# blumenland.net
KiCad netlist of a schematic drawn in EAGLE
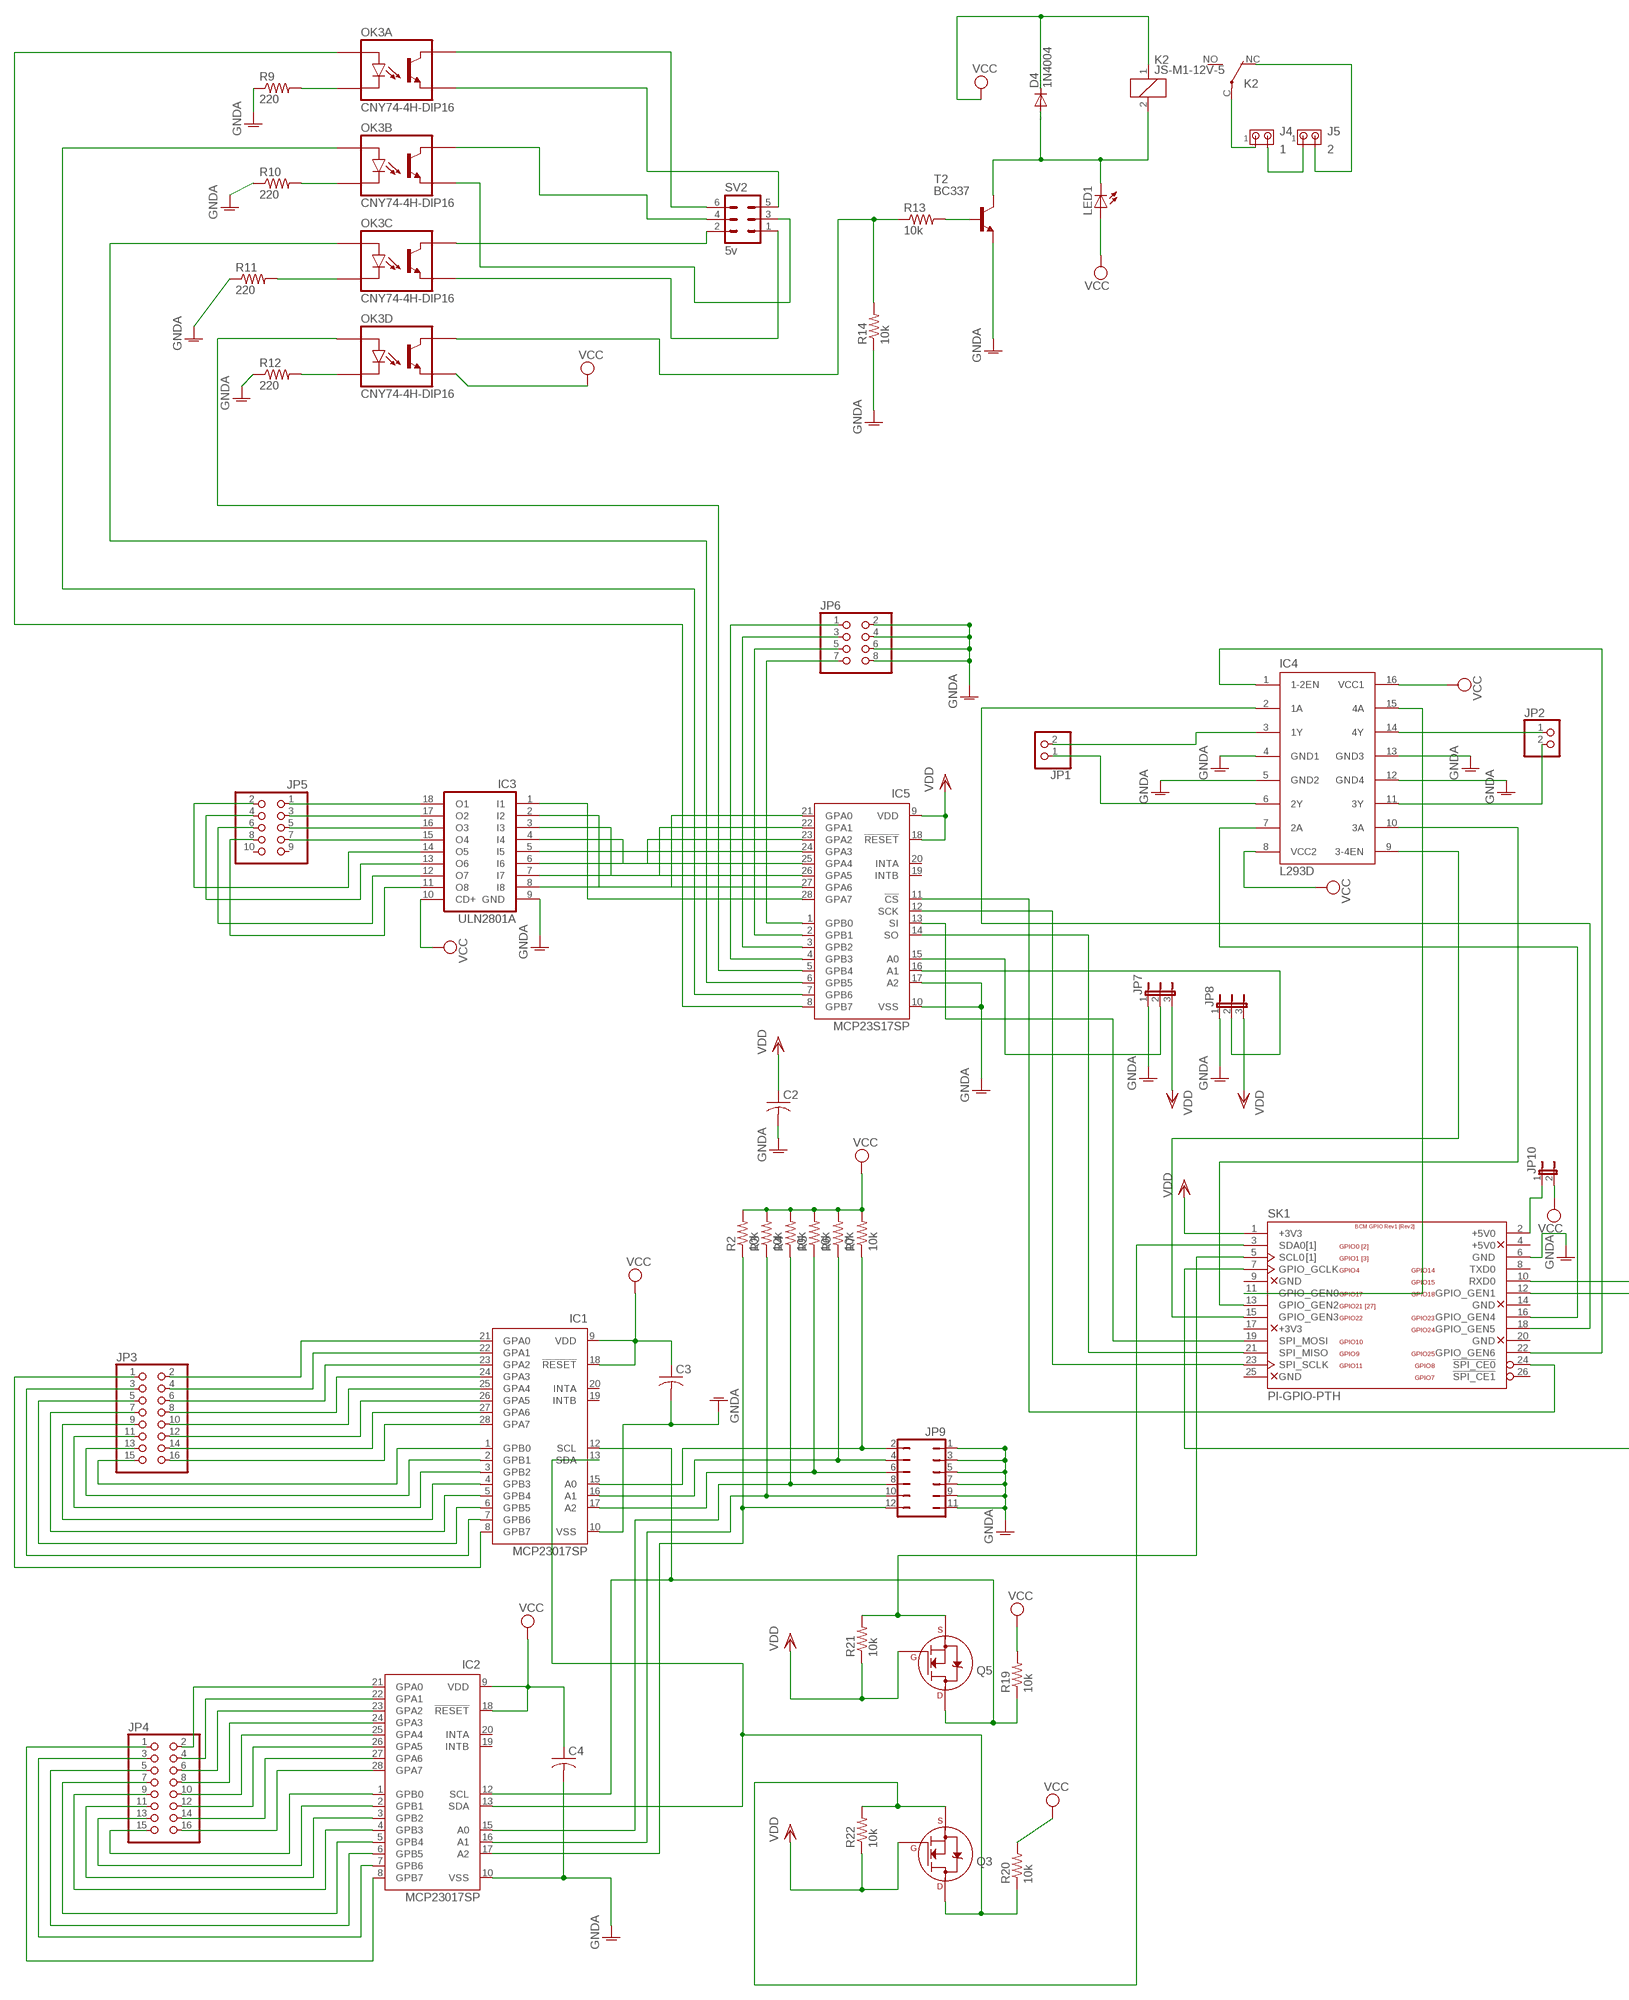
[diagram p0: schematic, sheet 1, part 1 of 2]
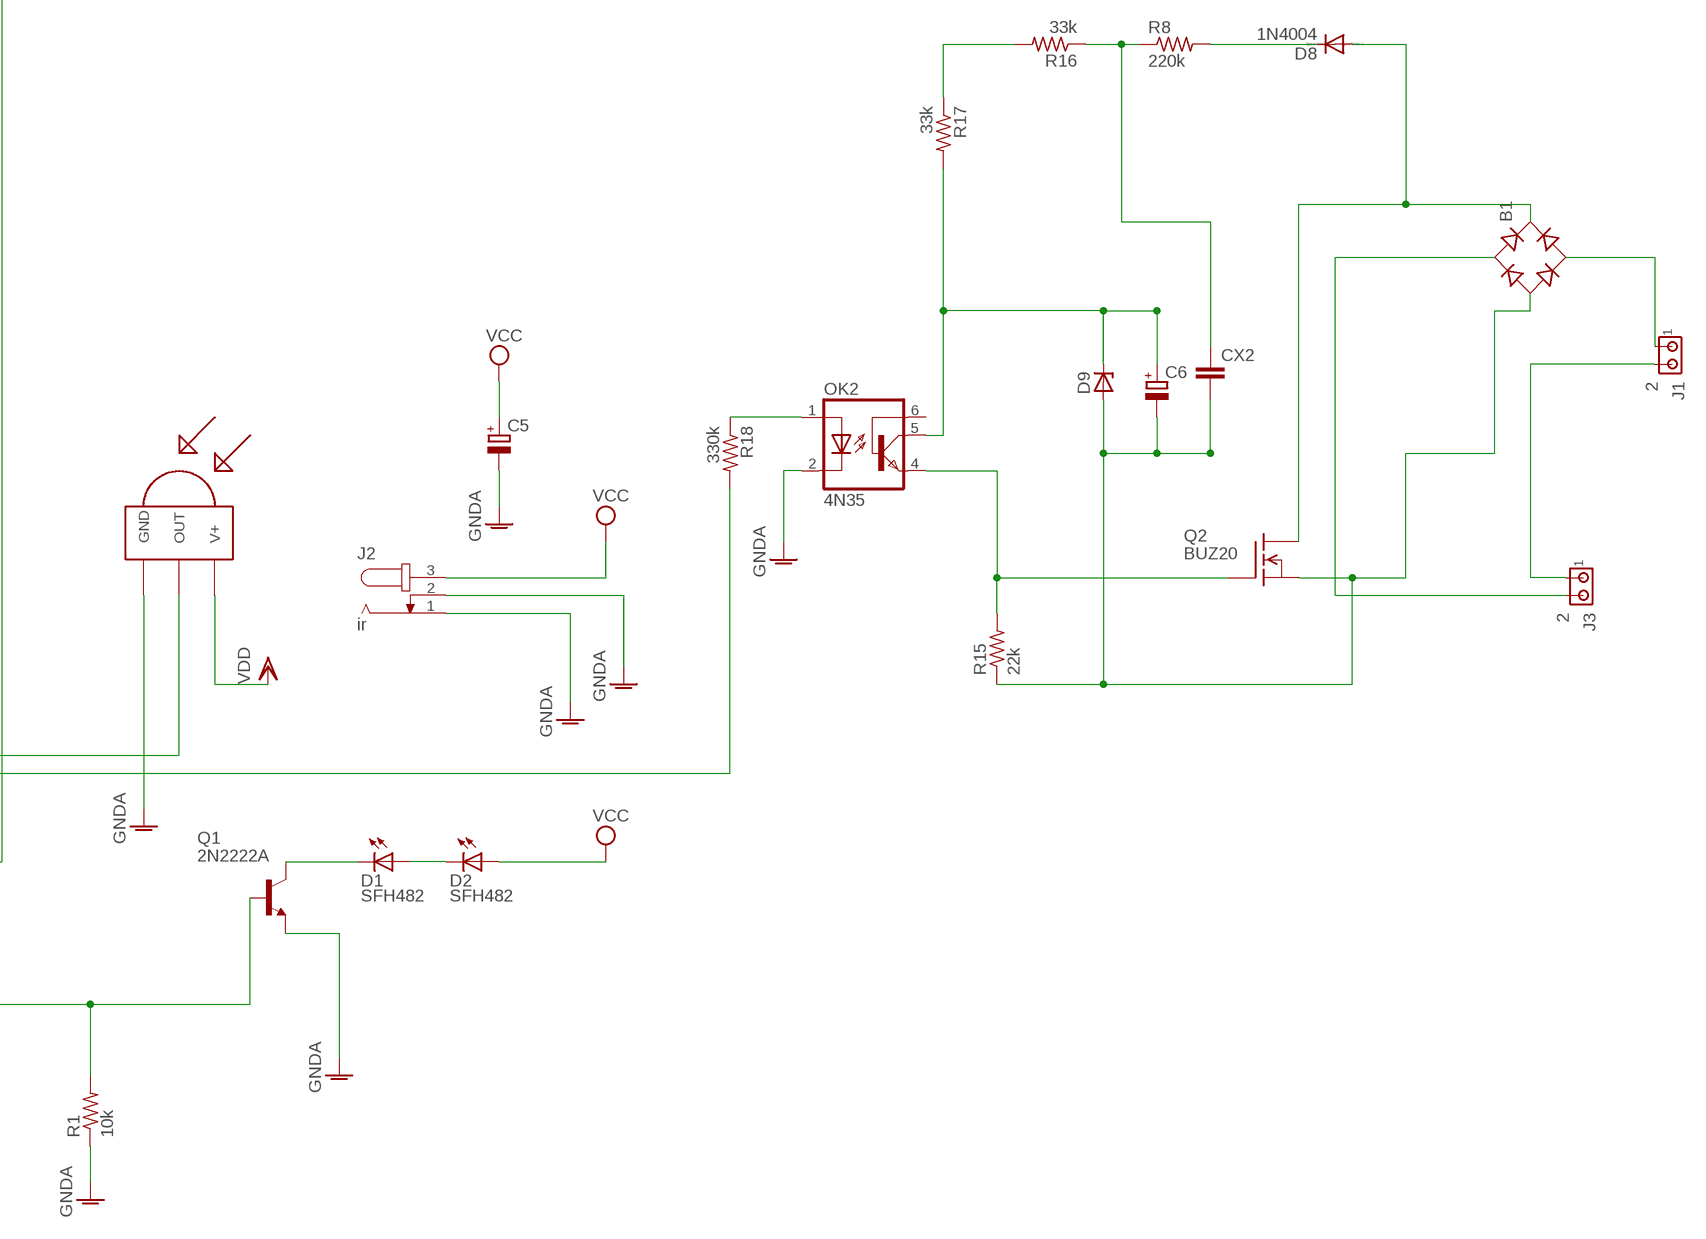
[diagram p1: schematic, sheet 1, part 2 of 2]

(export (version "E")
  (design (tool "Eeschema 10.0.6"))
  (components
    (comp (ref "B1")
      (value "RB1A")
      (footprint "eagle-import:RB1A")
      (libsource (lib "eagle-import") (part "RB1A"))
    )
    (comp (ref "C2")
      (value "C-US025-025X050")
      (footprint "eagle-import:C025-025X050")
      (libsource (lib "eagle-import") (part "C-US025-025X050"))
    )
    (comp (ref "C3")
      (value "C-US025-025X050")
      (footprint "eagle-import:C025-025X050")
      (libsource (lib "eagle-import") (part "C-US025-025X050"))
    )
    (comp (ref "C4")
      (value "C-US025-025X050")
      (footprint "eagle-import:C025-025X050")
      (libsource (lib "eagle-import") (part "C-US025-025X050"))
    )
    (comp (ref "C5")
      (value "CPOL-EUE2-5")
      (footprint "eagle-import:E2-5")
      (libsource (lib "eagle-import") (part "CPOL-EUE2-5"))
    )
    (comp (ref "C6")
      (value "CPOL-EUE2.5-5")
      (footprint "eagle-import:E2,5-5")
      (libsource (lib "eagle-import") (part "CPOL-EUE2.5-5"))
    )
    (comp (ref "CX2")
      (value "CXXC10B6")
      (footprint "eagle-import:XC10B6")
      (libsource (lib "eagle-import") (part "CXXC10B6"))
    )
    (comp (ref "D1")
      (value "SFH482")
      (footprint "eagle-import:SFH482")
      (libsource (lib "eagle-import") (part "SFH482"))
    )
    (comp (ref "D2")
      (value "SFH482")
      (footprint "eagle-import:SFH482")
      (libsource (lib "eagle-import") (part "SFH482"))
    )
    (comp (ref "D4")
      (value "1N4004")
      (footprint "eagle-import:DO41-10")
      (libsource (lib "eagle-import") (part "1N4004"))
    )
    (comp (ref "D8")
      (value "1N4004")
      (footprint "eagle-import:DO41-10")
      (libsource (lib "eagle-import") (part "1N4004"))
    )
    (comp (ref "D9")
      (value "ZENER-DIODEDO41Z10")
      (footprint "eagle-import:DO41Z10")
      (libsource (lib "eagle-import") (part "ZENER-DIODEDO41Z10"))
    )
    (comp (ref "IC1")
      (value "MCP23017SP")
      (footprint "eagle-import:DIL28-3")
      (fields (field (name "MF") "MICROCHIP") (field (name "MPN") "MCP23017-E/SP"))
      (libsource (lib "eagle-import") (part "MCP23017SP"))
    )
    (comp (ref "IC2")
      (value "MCP23017SP")
      (footprint "eagle-import:DIL28-3")
      (fields (field (name "MF") "MICROCHIP") (field (name "MPN") "MCP23017-E/SP"))
      (libsource (lib "eagle-import") (part "MCP23017SP"))
    )
    (comp (ref "IC3")
      (value "ULN2801A")
      (footprint "eagle-import:DIL18")
      (libsource (lib "eagle-import") (part "ULN2801A"))
    )
    (comp (ref "IC4")
      (value "L293D")
      (footprint "eagle-import:DIL16")
      (libsource (lib "eagle-import") (part "L293D"))
    )
    (comp (ref "IC5")
      (value "MCP23S17SP")
      (footprint "eagle-import:DIL28-3")
      (fields (field (name "MF") "MICROCHIP") (field (name "MPN") "MCP23S17-E/SP"))
      (libsource (lib "eagle-import") (part "MCP23S17SP"))
    )
    (comp (ref "J1")
      (value "2")
      (footprint "eagle-import:1X2MTA")
      (libsource (lib "eagle-import") (part "MTA02-156"))
    )
    (comp (ref "J2")
      (value "ir")
      (footprint "eagle-import:SPC4077")
      (libsource (lib "eagle-import") (part "JACK-PLUG0"))
    )
    (comp (ref "J3")
      (value "2")
      (footprint "eagle-import:1X2MTA")
      (libsource (lib "eagle-import") (part "MTA02-156"))
    )
    (comp (ref "J4")
      (value "1")
      (footprint "eagle-import:1X2MTA")
      (libsource (lib "eagle-import") (part "MTA02-156"))
    )
    (comp (ref "J5")
      (value "2")
      (footprint "eagle-import:1X2MTA")
      (libsource (lib "eagle-import") (part "MTA02-156"))
    )
    (comp (ref "JP1")
      (value "PINHD-1X2")
      (footprint "eagle-import:1X02")
      (libsource (lib "eagle-import") (part "PINHD-1X2"))
    )
    (comp (ref "JP2")
      (value "PINHD-1X2")
      (footprint "eagle-import:1X02")
      (libsource (lib "eagle-import") (part "PINHD-1X2"))
    )
    (comp (ref "JP3")
      (value "PINHD-2X8")
      (footprint "eagle-import:2X08")
      (libsource (lib "eagle-import") (part "PINHD-2X8"))
    )
    (comp (ref "JP4")
      (value "PINHD-2X8")
      (footprint "eagle-import:2X08")
      (libsource (lib "eagle-import") (part "PINHD-2X8"))
    )
    (comp (ref "JP5")
      (value "PINHD-2X5")
      (footprint "eagle-import:2X05")
      (libsource (lib "eagle-import") (part "PINHD-2X5"))
    )
    (comp (ref "JP6")
      (value "PINHD-2X4")
      (footprint "eagle-import:2X04")
      (libsource (lib "eagle-import") (part "PINHD-2X4"))
    )
    (comp (ref "JP7")
      (value "JP2E")
      (footprint "eagle-import:JP2")
      (libsource (lib "eagle-import") (part "JP2E"))
    )
    (comp (ref "JP8")
      (value "JP2E")
      (footprint "eagle-import:JP2")
      (libsource (lib "eagle-import") (part "JP2E"))
    )
    (comp (ref "JP9")
      (value "JP6Q")
      (footprint "eagle-import:JP6Q")
      (libsource (lib "eagle-import") (part "JP6Q"))
    )
    (comp (ref "JP10")
      (value "JP1E")
      (footprint "eagle-import:JP1")
      (libsource (lib "eagle-import") (part "JP1E"))
    )
    (comp (ref "K2")
      (value "JS-M1-12V-5")
      (footprint "eagle-import:JS-M")
      (fields (field (name "MF") "FARNELL") (field (name "MPN") "JSM1-12V-5"))
      (libsource (lib "eagle-import") (part "JS-M1-12V-5"))
    )
    (comp (ref "LED1")
      (value "LED5MM")
      (footprint "eagle-import:LED5MM")
      (libsource (lib "eagle-import") (part "LED5MM"))
    )
    (comp (ref "OK2")
      (value "4N35")
      (footprint "eagle-import:DIL06")
      (fields (field (name "MF") "FAIRCHILD SEMICONDUCTOR"))
      (libsource (lib "eagle-import") (part "4N35"))
    )
    (comp (ref "OK3")
      (value "CNY74-4H-DIP16")
      (footprint "eagle-import:DIL16-3")
      (libsource (lib "eagle-import") (part "CNY74-4H-DIP16"))
    )
    (comp (ref "Q1")
      (value "2N2222A")
      (footprint "eagle-import:TO18")
      (libsource (lib "eagle-import") (part "2N2222A"))
    )
    (comp (ref "Q2")
      (value "BUZ20")
      (footprint "eagle-import:TO220")
      (libsource (lib "eagle-import") (part "BUZ20"))
    )
    (comp (ref "Q3")
      (value "2N7000_TO92")
      (footprint "eagle-import:TO-92")
      (libsource (lib "eagle-import") (part "2N700_TO920"))
    )
    (comp (ref "Q5")
      (value "2N7000_TO92")
      (footprint "eagle-import:TO-92")
      (libsource (lib "eagle-import") (part "2N700_TO920"))
    )
    (comp (ref "R1")
      (value "10k")
      (footprint "eagle-import:0207_10")
      (libsource (lib "eagle-import") (part "R-US_0207/10"))
    )
    (comp (ref "R2")
      (value "10k")
      (footprint "eagle-import:0207_10")
      (libsource (lib "eagle-import") (part "R-US_0207/10"))
    )
    (comp (ref "R3")
      (value "10k")
      (footprint "eagle-import:0207_10")
      (libsource (lib "eagle-import") (part "R-US_0207/10"))
    )
    (comp (ref "R4")
      (value "10k")
      (footprint "eagle-import:0207_10")
      (libsource (lib "eagle-import") (part "R-US_0207/10"))
    )
    (comp (ref "R5")
      (value "10k")
      (footprint "eagle-import:0207_10")
      (libsource (lib "eagle-import") (part "R-US_0207/10"))
    )
    (comp (ref "R6")
      (value "10k")
      (footprint "eagle-import:0207_10")
      (libsource (lib "eagle-import") (part "R-US_0207/10"))
    )
    (comp (ref "R7")
      (value "10k")
      (footprint "eagle-import:0207_10")
      (libsource (lib "eagle-import") (part "R-US_0207/10"))
    )
    (comp (ref "R8")
      (value "220k")
      (footprint "eagle-import:0207_10")
      (libsource (lib "eagle-import") (part "R-US_0207/10"))
    )
    (comp (ref "R9")
      (value "220")
      (footprint "eagle-import:0204_7")
      (libsource (lib "eagle-import") (part "R-US_0204/7"))
    )
    (comp (ref "R10")
      (value "220")
      (footprint "eagle-import:0204_7")
      (libsource (lib "eagle-import") (part "R-US_0204/7"))
    )
    (comp (ref "R11")
      (value "220")
      (footprint "eagle-import:0204_7")
      (libsource (lib "eagle-import") (part "R-US_0204/7"))
    )
    (comp (ref "R12")
      (value "220")
      (footprint "eagle-import:0204_7")
      (libsource (lib "eagle-import") (part "R-US_0204/7"))
    )
    (comp (ref "R13")
      (value "10k")
      (footprint "eagle-import:0204_7")
      (libsource (lib "eagle-import") (part "R-US_0204/7"))
    )
    (comp (ref "R14")
      (value "10k")
      (footprint "eagle-import:0204_7")
      (libsource (lib "eagle-import") (part "R-US_0204/7"))
    )
    (comp (ref "R15")
      (value "22k")
      (footprint "eagle-import:0207_10")
      (libsource (lib "eagle-import") (part "R-US_0207/10"))
    )
    (comp (ref "R16")
      (value "33k")
      (footprint "eagle-import:0207_10")
      (libsource (lib "eagle-import") (part "R-US_0207/10"))
    )
    (comp (ref "R17")
      (value "33k")
      (footprint "eagle-import:0207_10")
      (libsource (lib "eagle-import") (part "R-US_0207/10"))
    )
    (comp (ref "R18")
      (value "330k")
      (footprint "eagle-import:0207_10")
      (libsource (lib "eagle-import") (part "R-US_0207/10"))
    )
    (comp (ref "R19")
      (value "10k")
      (footprint "eagle-import:0207_10")
      (libsource (lib "eagle-import") (part "R-US_0207/10"))
    )
    (comp (ref "R20")
      (value "10k")
      (footprint "eagle-import:0207_10")
      (libsource (lib "eagle-import") (part "R-US_0207/10"))
    )
    (comp (ref "R21")
      (value "10k")
      (footprint "eagle-import:0207_10")
      (libsource (lib "eagle-import") (part "R-US_0207/10"))
    )
    (comp (ref "R22")
      (value "10k")
      (footprint "eagle-import:0207_10")
      (libsource (lib "eagle-import") (part "R-US_0207/10"))
    )
    (comp (ref "SK1")
      (value "PI-GPIO-PTH")
      (footprint "eagle-import:GPIO-CONNECTOR")
      (libsource (lib "eagle-import") (part "PI-GPIO-PTH"))
    )
    (comp (ref "SV2")
      (value "5v")
      (footprint "eagle-import:MA03-2")
      (libsource (lib "eagle-import") (part "MA03-2"))
    )
    (comp (ref "T2")
      (value "BC337")
      (footprint "eagle-import:TO92")
      (libsource (lib "eagle-import") (part "BC337"))
    )
    (comp (ref "U$1")
      (value "TSOP4838")
      (footprint "eagle-import:TSOP18XX")
      (libsource (lib "eagle-import") (part "TSOP4838"))
    )
  )
  (nets
    (net (code "1") (name "GNDA") (class "Default")
      (node (ref "C2") (pin "2") (pinfunction "2_2") (pintype "passive"))
      (node (ref "C3") (pin "2") (pinfunction "2_2") (pintype "passive"))
      (node (ref "C4") (pin "2") (pinfunction "2_2") (pintype "passive"))
      (node (ref "C5") (pin "-") (pinfunction "-_-") (pintype "passive"))
      (node (ref "IC1") (pin "10") (pinfunction "VSS_10") (pintype "power_in"))
      (node (ref "IC2") (pin "10") (pinfunction "VSS_10") (pintype "power_in"))
      (node (ref "IC3") (pin "9") (pinfunction "GND_9") (pintype "power_in"))
      (node (ref "IC4") (pin "12") (pinfunction "GND4_12") (pintype "power_in"))
      (node (ref "IC4") (pin "13") (pinfunction "GND3_13") (pintype "power_in"))
      (node (ref "IC4") (pin "4") (pinfunction "GND1_4") (pintype "power_in"))
      (node (ref "IC4") (pin "5") (pinfunction "GND2_5") (pintype "power_in"))
      (node (ref "IC5") (pin "10") (pinfunction "VSS_10") (pintype "power_in"))
      (node (ref "IC5") (pin "17") (pinfunction "A2_17") (pintype "input"))
      (node (ref "J2") (pin "1") (pinfunction "1_1") (pintype "passive"))
      (node (ref "J2") (pin "2") (pinfunction "2_2") (pintype "passive"))
      (node (ref "JP6") (pin "2") (pinfunction "2_2") (pintype "passive"))
      (node (ref "JP6") (pin "4") (pinfunction "4_4") (pintype "passive"))
      (node (ref "JP6") (pin "6") (pinfunction "6_6") (pintype "passive"))
      (node (ref "JP6") (pin "8") (pinfunction "8_8") (pintype "passive"))
      (node (ref "JP7") (pin "1") (pinfunction "1_1") (pintype "passive"))
      (node (ref "JP8") (pin "1") (pinfunction "1_1") (pintype "passive"))
      (node (ref "JP9") (pin "1") (pinfunction "1_1") (pintype "passive"))
      (node (ref "JP9") (pin "11") (pinfunction "11_11") (pintype "passive"))
      (node (ref "JP9") (pin "3") (pinfunction "3_3") (pintype "passive"))
      (node (ref "JP9") (pin "5") (pinfunction "5_5") (pintype "passive"))
      (node (ref "JP9") (pin "7") (pinfunction "7_7") (pintype "passive"))
      (node (ref "JP9") (pin "9") (pinfunction "9_9") (pintype "passive"))
      (node (ref "OK2") (pin "2") (pinfunction "C_2") (pintype "passive"))
      (node (ref "Q1") (pin "1") (pinfunction "E_1") (pintype "passive"))
      (node (ref "R1") (pin "1") (pinfunction "1_1") (pintype "passive"))
      (node (ref "R10") (pin "1") (pinfunction "1_1") (pintype "passive"))
      (node (ref "R11") (pin "1") (pinfunction "1_1") (pintype "passive"))
      (node (ref "R12") (pin "1") (pinfunction "1_1") (pintype "passive"))
      (node (ref "R14") (pin "1") (pinfunction "1_1") (pintype "passive"))
      (node (ref "R9") (pin "1") (pinfunction "1_1") (pintype "passive"))
      (node (ref "SK1") (pin "6") (pinfunction "GND_6") (pintype "power_in"))
      (node (ref "T2") (pin "1") (pinfunction "E_1") (pintype "passive"))
      (node (ref "U$1") (pin "GND") (pinfunction "GND_GND") (pintype "bidirectional"))
    )
    (net (code "2") (name "Net-(B1-PadAC1)") (class "Default")
      (node (ref "B1") (pin "AC1") (pinfunction "AC1_AC1") (pintype "passive"))
      (node (ref "J3") (pin "2") (pinfunction "2_2") (pintype "passive"))
    )
    (net (code "3") (name "Net-(B1-PadAC2)") (class "Default")
      (node (ref "B1") (pin "AC2") (pinfunction "AC2_AC2") (pintype "passive"))
      (node (ref "J1") (pin "1") (pinfunction "1_1") (pintype "passive"))
    )
    (net (code "4") (name "Net-(CX2-Pad1)") (class "Default")
      (node (ref "CX2") (pin "1") (pinfunction "1_1") (pintype "passive"))
      (node (ref "R16") (pin "1") (pinfunction "1_1") (pintype "passive"))
      (node (ref "R8") (pin "1") (pinfunction "1_1") (pintype "passive"))
    )
    (net (code "5") (name "Net-(D1-C)") (class "Default")
      (node (ref "D1") (pin "K") (pinfunction "C_K") (pintype "passive"))
      (node (ref "Q1") (pin "3") (pinfunction "C_3") (pintype "passive"))
    )
    (net (code "6") (name "Net-(D2-C)") (class "Default")
      (node (ref "D1") (pin "A") (pinfunction "A_A") (pintype "passive"))
      (node (ref "D2") (pin "K") (pinfunction "C_K") (pintype "passive"))
    )
    (net (code "7") (name "Net-(D8-PadC)") (class "Default")
      (node (ref "D8") (pin "C") (pinfunction "C_C") (pintype "passive"))
      (node (ref "R8") (pin "2") (pinfunction "2_2") (pintype "passive"))
    )
    (net (code "8") (name "Net-(IC1-A0)") (class "Default")
      (node (ref "IC1") (pin "15") (pinfunction "A0_15") (pintype "input"))
      (node (ref "JP9") (pin "2") (pinfunction "2_2") (pintype "passive"))
      (node (ref "R7") (pin "1") (pinfunction "1_1") (pintype "passive"))
    )
    (net (code "9") (name "Net-(IC1-A1)") (class "Default")
      (node (ref "IC1") (pin "16") (pinfunction "A1_16") (pintype "input"))
      (node (ref "JP9") (pin "4") (pinfunction "4_4") (pintype "passive"))
      (node (ref "R6") (pin "1") (pinfunction "1_1") (pintype "passive"))
    )
    (net (code "10") (name "Net-(IC1-A2)") (class "Default")
      (node (ref "IC1") (pin "17") (pinfunction "A2_17") (pintype "input"))
      (node (ref "JP9") (pin "6") (pinfunction "6_6") (pintype "passive"))
      (node (ref "R5") (pin "1") (pinfunction "1_1") (pintype "passive"))
    )
    (net (code "11") (name "Net-(IC1-GPA0)") (class "Default")
      (node (ref "IC1") (pin "21") (pinfunction "GPA0_21") (pintype "bidirectional"))
      (node (ref "JP3") (pin "2") (pinfunction "2_2") (pintype "passive"))
    )
    (net (code "12") (name "Net-(IC1-GPA1)") (class "Default")
      (node (ref "IC1") (pin "22") (pinfunction "GPA1_22") (pintype "bidirectional"))
      (node (ref "JP3") (pin "4") (pinfunction "4_4") (pintype "passive"))
    )
    (net (code "13") (name "Net-(IC1-GPA2)") (class "Default")
      (node (ref "IC1") (pin "23") (pinfunction "GPA2_23") (pintype "bidirectional"))
      (node (ref "JP3") (pin "6") (pinfunction "6_6") (pintype "passive"))
    )
    (net (code "14") (name "Net-(IC1-GPA3)") (class "Default")
      (node (ref "IC1") (pin "24") (pinfunction "GPA3_24") (pintype "bidirectional"))
      (node (ref "JP3") (pin "8") (pinfunction "8_8") (pintype "passive"))
    )
    (net (code "15") (name "Net-(IC1-GPA4)") (class "Default")
      (node (ref "IC1") (pin "25") (pinfunction "GPA4_25") (pintype "bidirectional"))
      (node (ref "JP3") (pin "10") (pinfunction "10_10") (pintype "passive"))
    )
    (net (code "16") (name "Net-(IC1-GPA5)") (class "Default")
      (node (ref "IC1") (pin "26") (pinfunction "GPA5_26") (pintype "bidirectional"))
      (node (ref "JP3") (pin "12") (pinfunction "12_12") (pintype "passive"))
    )
    (net (code "17") (name "Net-(IC1-GPA6)") (class "Default")
      (node (ref "IC1") (pin "27") (pinfunction "GPA6_27") (pintype "bidirectional"))
      (node (ref "JP3") (pin "14") (pinfunction "14_14") (pintype "passive"))
    )
    (net (code "18") (name "Net-(IC1-GPA7)") (class "Default")
      (node (ref "IC1") (pin "28") (pinfunction "GPA7_28") (pintype "bidirectional"))
      (node (ref "JP3") (pin "16") (pinfunction "16_16") (pintype "passive"))
    )
    (net (code "19") (name "Net-(IC1-GPB0)") (class "Default")
      (node (ref "IC1") (pin "1") (pinfunction "GPB0_1") (pintype "bidirectional"))
      (node (ref "JP3") (pin "15") (pinfunction "15_15") (pintype "passive"))
    )
    (net (code "20") (name "Net-(IC1-GPB1)") (class "Default")
      (node (ref "IC1") (pin "2") (pinfunction "GPB1_2") (pintype "bidirectional"))
      (node (ref "JP3") (pin "13") (pinfunction "13_13") (pintype "passive"))
    )
    (net (code "21") (name "Net-(IC1-GPB2)") (class "Default")
      (node (ref "IC1") (pin "3") (pinfunction "GPB2_3") (pintype "bidirectional"))
      (node (ref "JP3") (pin "11") (pinfunction "11_11") (pintype "passive"))
    )
    (net (code "22") (name "Net-(IC1-GPB3)") (class "Default")
      (node (ref "IC1") (pin "4") (pinfunction "GPB3_4") (pintype "bidirectional"))
      (node (ref "JP3") (pin "9") (pinfunction "9_9") (pintype "passive"))
    )
    (net (code "23") (name "Net-(IC1-GPB4)") (class "Default")
      (node (ref "IC1") (pin "5") (pinfunction "GPB4_5") (pintype "bidirectional"))
      (node (ref "JP3") (pin "7") (pinfunction "7_7") (pintype "passive"))
    )
    (net (code "24") (name "Net-(IC1-GPB5)") (class "Default")
      (node (ref "IC1") (pin "6") (pinfunction "GPB5_6") (pintype "bidirectional"))
      (node (ref "JP3") (pin "5") (pinfunction "5_5") (pintype "passive"))
    )
    (net (code "25") (name "Net-(IC1-GPB6)") (class "Default")
      (node (ref "IC1") (pin "7") (pinfunction "GPB6_7") (pintype "bidirectional"))
      (node (ref "JP3") (pin "3") (pinfunction "3_3") (pintype "passive"))
    )
    (net (code "26") (name "Net-(IC1-GPB7)") (class "Default")
      (node (ref "IC1") (pin "8") (pinfunction "GPB7_8") (pintype "bidirectional"))
      (node (ref "JP3") (pin "1") (pinfunction "1_1") (pintype "passive"))
    )
    (net (code "27") (name "Net-(IC1-SCL)") (class "Default")
      (node (ref "IC1") (pin "12") (pinfunction "SCL_12") (pintype "input"))
      (node (ref "IC2") (pin "12") (pinfunction "SCL_12") (pintype "input"))
      (node (ref "Q5") (pin "3") (pinfunction "D_3") (pintype "bidirectional"))
      (node (ref "R19") (pin "1") (pinfunction "1_1") (pintype "passive"))
    )
    (net (code "28") (name "Net-(IC1-SDA)") (class "Default")
      (node (ref "IC1") (pin "13") (pinfunction "SDA_13") (pintype "bidirectional"))
      (node (ref "IC2") (pin "13") (pinfunction "SDA_13") (pintype "bidirectional"))
      (node (ref "Q3") (pin "3") (pinfunction "D_3") (pintype "bidirectional"))
      (node (ref "R20") (pin "1") (pinfunction "1_1") (pintype "passive"))
    )
    (net (code "29") (name "Net-(IC2-A0)") (class "Default")
      (node (ref "IC2") (pin "15") (pinfunction "A0_15") (pintype "input"))
      (node (ref "JP9") (pin "8") (pinfunction "8_8") (pintype "passive"))
      (node (ref "R4") (pin "1") (pinfunction "1_1") (pintype "passive"))
    )
    (net (code "30") (name "Net-(IC2-A1)") (class "Default")
      (node (ref "IC2") (pin "16") (pinfunction "A1_16") (pintype "input"))
      (node (ref "JP9") (pin "10") (pinfunction "10_10") (pintype "passive"))
      (node (ref "R3") (pin "1") (pinfunction "1_1") (pintype "passive"))
    )
    (net (code "31") (name "Net-(IC2-A2)") (class "Default")
      (node (ref "IC2") (pin "17") (pinfunction "A2_17") (pintype "input"))
      (node (ref "JP9") (pin "12") (pinfunction "12_12") (pintype "passive"))
      (node (ref "R2") (pin "1") (pinfunction "1_1") (pintype "passive"))
    )
    (net (code "32") (name "Net-(IC2-GPA0)") (class "Default")
      (node (ref "IC2") (pin "21") (pinfunction "GPA0_21") (pintype "bidirectional"))
      (node (ref "JP4") (pin "2") (pinfunction "2_2") (pintype "passive"))
    )
    (net (code "33") (name "Net-(IC2-GPA1)") (class "Default")
      (node (ref "IC2") (pin "22") (pinfunction "GPA1_22") (pintype "bidirectional"))
      (node (ref "JP4") (pin "4") (pinfunction "4_4") (pintype "passive"))
    )
    (net (code "34") (name "Net-(IC2-GPA2)") (class "Default")
      (node (ref "IC2") (pin "23") (pinfunction "GPA2_23") (pintype "bidirectional"))
      (node (ref "JP4") (pin "6") (pinfunction "6_6") (pintype "passive"))
    )
    (net (code "35") (name "Net-(IC2-GPA3)") (class "Default")
      (node (ref "IC2") (pin "24") (pinfunction "GPA3_24") (pintype "bidirectional"))
      (node (ref "JP4") (pin "8") (pinfunction "8_8") (pintype "passive"))
    )
    (net (code "36") (name "Net-(IC2-GPA4)") (class "Default")
      (node (ref "IC2") (pin "25") (pinfunction "GPA4_25") (pintype "bidirectional"))
      (node (ref "JP4") (pin "10") (pinfunction "10_10") (pintype "passive"))
    )
    (net (code "37") (name "Net-(IC2-GPA5)") (class "Default")
      (node (ref "IC2") (pin "26") (pinfunction "GPA5_26") (pintype "bidirectional"))
      (node (ref "JP4") (pin "12") (pinfunction "12_12") (pintype "passive"))
    )
    (net (code "38") (name "Net-(IC2-GPA6)") (class "Default")
      (node (ref "IC2") (pin "27") (pinfunction "GPA6_27") (pintype "bidirectional"))
      (node (ref "JP4") (pin "14") (pinfunction "14_14") (pintype "passive"))
    )
    (net (code "39") (name "Net-(IC2-GPA7)") (class "Default")
      (node (ref "IC2") (pin "28") (pinfunction "GPA7_28") (pintype "bidirectional"))
      (node (ref "JP4") (pin "16") (pinfunction "16_16") (pintype "passive"))
    )
    (net (code "40") (name "Net-(IC2-GPB0)") (class "Default")
      (node (ref "IC2") (pin "1") (pinfunction "GPB0_1") (pintype "bidirectional"))
      (node (ref "JP4") (pin "15") (pinfunction "15_15") (pintype "passive"))
    )
    (net (code "41") (name "Net-(IC2-GPB1)") (class "Default")
      (node (ref "IC2") (pin "2") (pinfunction "GPB1_2") (pintype "bidirectional"))
      (node (ref "JP4") (pin "13") (pinfunction "13_13") (pintype "passive"))
    )
    (net (code "42") (name "Net-(IC2-GPB2)") (class "Default")
      (node (ref "IC2") (pin "3") (pinfunction "GPB2_3") (pintype "bidirectional"))
      (node (ref "JP4") (pin "11") (pinfunction "11_11") (pintype "passive"))
    )
    (net (code "43") (name "Net-(IC2-GPB3)") (class "Default")
      (node (ref "IC2") (pin "4") (pinfunction "GPB3_4") (pintype "bidirectional"))
      (node (ref "JP4") (pin "9") (pinfunction "9_9") (pintype "passive"))
    )
    (net (code "44") (name "Net-(IC2-GPB4)") (class "Default")
      (node (ref "IC2") (pin "5") (pinfunction "GPB4_5") (pintype "bidirectional"))
      (node (ref "JP4") (pin "7") (pinfunction "7_7") (pintype "passive"))
    )
    (net (code "45") (name "Net-(IC2-GPB5)") (class "Default")
      (node (ref "IC2") (pin "6") (pinfunction "GPB5_6") (pintype "bidirectional"))
      (node (ref "JP4") (pin "5") (pinfunction "5_5") (pintype "passive"))
    )
    (net (code "46") (name "Net-(IC2-GPB6)") (class "Default")
      (node (ref "IC2") (pin "7") (pinfunction "GPB6_7") (pintype "bidirectional"))
      (node (ref "JP4") (pin "3") (pinfunction "3_3") (pintype "passive"))
    )
    (net (code "47") (name "Net-(IC2-GPB7)") (class "Default")
      (node (ref "IC2") (pin "8") (pinfunction "GPB7_8") (pintype "bidirectional"))
      (node (ref "JP4") (pin "1") (pinfunction "1_1") (pintype "passive"))
    )
    (net (code "48") (name "Net-(IC3-I1)") (class "Default")
      (node (ref "IC3") (pin "1") (pinfunction "I1_1") (pintype "input"))
      (node (ref "IC5") (pin "28") (pinfunction "GPA7_28") (pintype "bidirectional"))
    )
    (net (code "49") (name "Net-(IC3-I2)") (class "Default")
      (node (ref "IC3") (pin "2") (pinfunction "I2_2") (pintype "input"))
      (node (ref "IC5") (pin "27") (pinfunction "GPA6_27") (pintype "bidirectional"))
    )
    (net (code "50") (name "Net-(IC3-I3)") (class "Default")
      (node (ref "IC3") (pin "3") (pinfunction "I3_3") (pintype "input"))
      (node (ref "IC5") (pin "26") (pinfunction "GPA5_26") (pintype "bidirectional"))
    )
    (net (code "51") (name "Net-(IC3-I4)") (class "Default")
      (node (ref "IC3") (pin "4") (pinfunction "I4_4") (pintype "input"))
      (node (ref "IC5") (pin "25") (pinfunction "GPA4_25") (pintype "bidirectional"))
    )
    (net (code "52") (name "Net-(IC3-I5)") (class "Default")
      (node (ref "IC3") (pin "5") (pinfunction "I5_5") (pintype "input"))
      (node (ref "IC5") (pin "24") (pinfunction "GPA3_24") (pintype "bidirectional"))
    )
    (net (code "53") (name "Net-(IC3-I6)") (class "Default")
      (node (ref "IC3") (pin "6") (pinfunction "I6_6") (pintype "input"))
      (node (ref "IC5") (pin "23") (pinfunction "GPA2_23") (pintype "bidirectional"))
    )
    (net (code "54") (name "Net-(IC3-I7)") (class "Default")
      (node (ref "IC3") (pin "7") (pinfunction "I7_7") (pintype "input"))
      (node (ref "IC5") (pin "22") (pinfunction "GPA1_22") (pintype "bidirectional"))
    )
    (net (code "55") (name "Net-(IC3-I8)") (class "Default")
      (node (ref "IC3") (pin "8") (pinfunction "I8_8") (pintype "input"))
      (node (ref "IC5") (pin "21") (pinfunction "GPA0_21") (pintype "bidirectional"))
    )
    (net (code "56") (name "Net-(IC3-O1)") (class "Default")
      (node (ref "IC3") (pin "18") (pinfunction "O1_18") (pintype "open_collector"))
      (node (ref "JP5") (pin "1") (pinfunction "1_1") (pintype "passive"))
    )
    (net (code "57") (name "Net-(IC3-O2)") (class "Default")
      (node (ref "IC3") (pin "17") (pinfunction "O2_17") (pintype "open_collector"))
      (node (ref "JP5") (pin "3") (pinfunction "3_3") (pintype "passive"))
    )
    (net (code "58") (name "Net-(IC3-O3)") (class "Default")
      (node (ref "IC3") (pin "16") (pinfunction "O3_16") (pintype "open_collector"))
      (node (ref "JP5") (pin "5") (pinfunction "5_5") (pintype "passive"))
    )
    (net (code "59") (name "Net-(IC3-O4)") (class "Default")
      (node (ref "IC3") (pin "15") (pinfunction "O4_15") (pintype "open_collector"))
      (node (ref "JP5") (pin "7") (pinfunction "7_7") (pintype "passive"))
    )
    (net (code "60") (name "Net-(IC3-O5)") (class "Default")
      (node (ref "IC3") (pin "14") (pinfunction "O5_14") (pintype "open_collector"))
      (node (ref "JP5") (pin "2") (pinfunction "2_2") (pintype "passive"))
    )
    (net (code "61") (name "Net-(IC3-O6)") (class "Default")
      (node (ref "IC3") (pin "13") (pinfunction "O6_13") (pintype "open_collector"))
      (node (ref "JP5") (pin "4") (pinfunction "4_4") (pintype "passive"))
    )
    (net (code "62") (name "Net-(IC3-O7)") (class "Default")
      (node (ref "IC3") (pin "12") (pinfunction "O7_12") (pintype "open_collector"))
      (node (ref "JP5") (pin "6") (pinfunction "6_6") (pintype "passive"))
    )
    (net (code "63") (name "Net-(IC3-O8)") (class "Default")
      (node (ref "IC3") (pin "11") (pinfunction "O8_11") (pintype "open_collector"))
      (node (ref "JP5") (pin "8") (pinfunction "8_8") (pintype "passive"))
    )
    (net (code "64") (name "Net-(IC4-1-2EN)") (class "Default")
      (node (ref "IC4") (pin "1") (pinfunction "1-2EN_1") (pintype "input"))
      (node (ref "SK1") (pin "22") (pinfunction "GPIO_GEN6_22") (pintype "bidirectional"))
    )
    (net (code "65") (name "Net-(IC4-1A)") (class "Default")
      (node (ref "IC4") (pin "2") (pinfunction "1A_2") (pintype "input"))
      (node (ref "SK1") (pin "18") (pinfunction "GPIO_GEN5_18") (pintype "bidirectional"))
    )
    (net (code "66") (name "Net-(IC4-1Y)") (class "Default")
      (node (ref "IC4") (pin "3") (pinfunction "1Y_3") (pintype "output"))
      (node (ref "JP1") (pin "2") (pinfunction "2_2") (pintype "passive"))
    )
    (net (code "67") (name "Net-(IC4-2A)") (class "Default")
      (node (ref "IC4") (pin "7") (pinfunction "2A_7") (pintype "input"))
      (node (ref "SK1") (pin "16") (pinfunction "GPIO_GEN4_16") (pintype "bidirectional"))
    )
    (net (code "68") (name "Net-(IC4-2Y)") (class "Default")
      (node (ref "IC4") (pin "6") (pinfunction "2Y_6") (pintype "output"))
      (node (ref "JP1") (pin "1") (pinfunction "1_1") (pintype "passive"))
    )
    (net (code "69") (name "Net-(IC4-3-4EN)") (class "Default")
      (node (ref "IC4") (pin "9") (pinfunction "3-4EN_9") (pintype "input"))
      (node (ref "SK1") (pin "15") (pinfunction "GPIO_GEN3_15") (pintype "bidirectional"))
    )
    (net (code "70") (name "Net-(IC4-3A)") (class "Default")
      (node (ref "IC4") (pin "10") (pinfunction "3A_10") (pintype "input"))
      (node (ref "SK1") (pin "13") (pinfunction "GPIO_GEN2_13") (pintype "bidirectional"))
    )
    (net (code "71") (name "Net-(IC4-3Y)") (class "Default")
      (node (ref "IC4") (pin "11") (pinfunction "3Y_11") (pintype "output"))
      (node (ref "JP2") (pin "2") (pinfunction "2_2") (pintype "passive"))
    )
    (net (code "72") (name "Net-(IC4-4A)") (class "Default")
      (node (ref "IC4") (pin "15") (pinfunction "4A_15") (pintype "input"))
      (node (ref "SK1") (pin "11") (pinfunction "GPIO_GEN0_11") (pintype "bidirectional"))
    )
    (net (code "73") (name "Net-(IC4-4Y)") (class "Default")
      (node (ref "IC4") (pin "14") (pinfunction "4Y_14") (pintype "output"))
      (node (ref "JP2") (pin "1") (pinfunction "1_1") (pintype "passive"))
    )
    (net (code "74") (name "Net-(IC5-A0)") (class "Default")
      (node (ref "IC5") (pin "15") (pinfunction "A0_15") (pintype "input"))
      (node (ref "JP7") (pin "2") (pinfunction "2_2") (pintype "passive"))
    )
    (net (code "75") (name "Net-(IC5-A1)") (class "Default")
      (node (ref "IC5") (pin "16") (pinfunction "A1_16") (pintype "input"))
      (node (ref "JP8") (pin "2") (pinfunction "2_2") (pintype "passive"))
    )
    (net (code "76") (name "Net-(IC5-GPB0)") (class "Default")
      (node (ref "IC5") (pin "1") (pinfunction "GPB0_1") (pintype "bidirectional"))
      (node (ref "JP6") (pin "7") (pinfunction "7_7") (pintype "passive"))
    )
    (net (code "77") (name "Net-(IC5-GPB1)") (class "Default")
      (node (ref "IC5") (pin "2") (pinfunction "GPB1_2") (pintype "bidirectional"))
      (node (ref "JP6") (pin "5") (pinfunction "5_5") (pintype "passive"))
    )
    (net (code "78") (name "Net-(IC5-GPB2)") (class "Default")
      (node (ref "IC5") (pin "3") (pinfunction "GPB2_3") (pintype "bidirectional"))
      (node (ref "JP6") (pin "3") (pinfunction "3_3") (pintype "passive"))
    )
    (net (code "79") (name "Net-(IC5-GPB3)") (class "Default")
      (node (ref "IC5") (pin "4") (pinfunction "GPB3_4") (pintype "bidirectional"))
      (node (ref "JP6") (pin "1") (pinfunction "1_1") (pintype "passive"))
    )
    (net (code "80") (name "Net-(IC5-GPB4)") (class "Default")
      (node (ref "IC5") (pin "5") (pinfunction "GPB4_5") (pintype "bidirectional"))
      (node (ref "OK3") (pin "8") (pinfunction "A1_8") (pintype "passive"))
    )
    (net (code "81") (name "Net-(IC5-GPB5)") (class "Default")
      (node (ref "IC5") (pin "6") (pinfunction "GPB5_6") (pintype "bidirectional"))
      (node (ref "OK3") (pin "5") (pinfunction "A1_5") (pintype "passive"))
    )
    (net (code "82") (name "Net-(IC5-GPB6)") (class "Default")
      (node (ref "IC5") (pin "7") (pinfunction "GPB6_7") (pintype "bidirectional"))
      (node (ref "OK3") (pin "4") (pinfunction "A1_4") (pintype "passive"))
    )
    (net (code "83") (name "Net-(IC5-GPB7)") (class "Default")
      (node (ref "IC5") (pin "8") (pinfunction "GPB7_8") (pintype "bidirectional"))
      (node (ref "OK3") (pin "1") (pinfunction "A1_1") (pintype "passive"))
    )
    (net (code "84") (name "Net-(IC5-SCK)") (class "Default")
      (node (ref "IC5") (pin "12") (pinfunction "SCK_12") (pintype "input"))
      (node (ref "SK1") (pin "23") (pinfunction "SPI_SCLK_23") (pintype "bidirectional"))
    )
    (net (code "85") (name "Net-(IC5-SI)") (class "Default")
      (node (ref "IC5") (pin "13") (pinfunction "SI_13") (pintype "input"))
      (node (ref "SK1") (pin "19") (pinfunction "SPI_MOSI_19") (pintype "bidirectional"))
    )
    (net (code "86") (name "Net-(IC5-SO)") (class "Default")
      (node (ref "IC5") (pin "14") (pinfunction "SO_14") (pintype "output"))
      (node (ref "SK1") (pin "21") (pinfunction "SPI_MISO_21") (pintype "bidirectional"))
    )
    (net (code "87") (name "Net-(IC5-~{CS})") (class "Default")
      (node (ref "IC5") (pin "11") (pinfunction "~{CS}_11") (pintype "input"))
      (node (ref "SK1") (pin "24") (pinfunction "~{SPI_CE0}_24") (pintype "bidirectional"))
    )
    (net (code "88") (name "Net-(J1-Pad2)") (class "Default")
      (node (ref "J1") (pin "2") (pinfunction "2_2") (pintype "passive"))
      (node (ref "J3") (pin "1") (pinfunction "1_1") (pintype "passive"))
    )
    (net (code "89") (name "Net-(J4-Pad2)") (class "Default")
      (node (ref "J4") (pin "2") (pinfunction "2_2") (pintype "passive"))
      (node (ref "J5") (pin "1") (pinfunction "1_1") (pintype "passive"))
    )
    (net (code "90") (name "Net-(K2B-O)") (class "Default")
      (node (ref "J5") (pin "2") (pinfunction "2_2") (pintype "passive"))
      (node (ref "K2") (pin "NC") (pinfunction "O_NC") (pintype "passive"))
    )
    (net (code "91") (name "Net-(K2B-P)") (class "Default")
      (node (ref "J4") (pin "1") (pinfunction "1_1") (pintype "passive"))
      (node (ref "K2") (pin "C") (pinfunction "P_C") (pintype "passive"))
    )
    (net (code "92") (name "Net-(LED1-C)") (class "Default")
      (node (ref "D4") (pin "A") (pinfunction "A_A") (pintype "passive"))
      (node (ref "K2") (pin "2") (pinfunction "2_2") (pintype "passive"))
      (node (ref "LED1") (pin "K") (pinfunction "C_K") (pintype "passive"))
      (node (ref "T2") (pin "3") (pinfunction "C_3") (pintype "passive"))
    )
    (net (code "93") (name "Net-(OK2-A)") (class "Default")
      (node (ref "OK2") (pin "1") (pinfunction "A_1") (pintype "passive"))
      (node (ref "R18") (pin "1") (pinfunction "1_1") (pintype "passive"))
    )
    (net (code "94") (name "Net-(OK2-COL)") (class "Default")
      (node (ref "C6") (pin "+") (pinfunction "+_+") (pintype "passive"))
      (node (ref "D9") (pin "C") (pinfunction "C_C") (pintype "passive"))
      (node (ref "OK2") (pin "5") (pinfunction "COL_5") (pintype "passive"))
      (node (ref "R17") (pin "2") (pinfunction "2_2") (pintype "passive"))
    )
    (net (code "95") (name "Net-(OK2-EMI)") (class "Default")
      (node (ref "OK2") (pin "4") (pinfunction "EMI_4") (pintype "passive"))
      (node (ref "Q2") (pin "1") (pinfunction "G_1") (pintype "passive"))
      (node (ref "R15") (pin "2") (pinfunction "2_2") (pintype "passive"))
    )
    (net (code "96") (name "Net-(OK3A-C1)") (class "Default")
      (node (ref "OK3") (pin "2") (pinfunction "C1_2") (pintype "passive"))
      (node (ref "R9") (pin "2") (pinfunction "2_2") (pintype "passive"))
    )
    (net (code "97") (name "Net-(OK3A-COLLECTOR1)") (class "Default")
      (node (ref "OK3") (pin "15") (pinfunction "COLLECTOR1_15") (pintype "passive"))
      (node (ref "SV2") (pin "6") (pinfunction "6_6") (pintype "passive"))
    )
    (net (code "98") (name "Net-(OK3A-EMITTER1)") (class "Default")
      (node (ref "OK3") (pin "16") (pinfunction "EMITTER1_16") (pintype "passive"))
      (node (ref "SV2") (pin "5") (pinfunction "5_5") (pintype "passive"))
    )
    (net (code "99") (name "Net-(OK3B-C1)") (class "Default")
      (node (ref "OK3") (pin "3") (pinfunction "C1_3") (pintype "passive"))
      (node (ref "R10") (pin "2") (pinfunction "2_2") (pintype "passive"))
    )
    (net (code "100") (name "Net-(OK3B-COLLECTOR1)") (class "Default")
      (node (ref "OK3") (pin "14") (pinfunction "COLLECTOR1_14") (pintype "passive"))
      (node (ref "SV2") (pin "4") (pinfunction "4_4") (pintype "passive"))
    )
    (net (code "101") (name "Net-(OK3B-EMITTER1)") (class "Default")
      (node (ref "OK3") (pin "13") (pinfunction "EMITTER1_13") (pintype "passive"))
      (node (ref "SV2") (pin "3") (pinfunction "3_3") (pintype "passive"))
    )
    (net (code "102") (name "Net-(OK3C-C1)") (class "Default")
      (node (ref "OK3") (pin "6") (pinfunction "C1_6") (pintype "passive"))
      (node (ref "R11") (pin "2") (pinfunction "2_2") (pintype "passive"))
    )
    (net (code "103") (name "Net-(OK3C-COLLECTOR1)") (class "Default")
      (node (ref "OK3") (pin "11") (pinfunction "COLLECTOR1_11") (pintype "passive"))
      (node (ref "SV2") (pin "2") (pinfunction "2_2") (pintype "passive"))
    )
    (net (code "104") (name "Net-(OK3C-EMITTER1)") (class "Default")
      (node (ref "OK3") (pin "12") (pinfunction "EMITTER1_12") (pintype "passive"))
      (node (ref "SV2") (pin "1") (pinfunction "1_1") (pintype "passive"))
    )
    (net (code "105") (name "Net-(OK3D-C1)") (class "Default")
      (node (ref "OK3") (pin "7") (pinfunction "C1_7") (pintype "passive"))
      (node (ref "R12") (pin "2") (pinfunction "2_2") (pintype "passive"))
    )
    (net (code "106") (name "Net-(OK3D-COLLECTOR1)") (class "Default")
      (node (ref "OK3") (pin "9") (pinfunction "COLLECTOR1_9") (pintype "passive"))
      (node (ref "R13") (pin "1") (pinfunction "1_1") (pintype "passive"))
      (node (ref "R14") (pin "2") (pinfunction "2_2") (pintype "passive"))
    )
    (net (code "107") (name "Net-(Q1-B)") (class "Default")
      (node (ref "Q1") (pin "2") (pinfunction "B_2") (pintype "passive"))
      (node (ref "R1") (pin "2") (pinfunction "2_2") (pintype "passive"))
      (node (ref "SK1") (pin "7") (pinfunction "GPIO_GCLK_7") (pintype "bidirectional"))
    )
    (net (code "108") (name "Net-(Q2-D)") (class "Default")
      (node (ref "B1") (pin "+") (pinfunction "+_+") (pintype "passive"))
      (node (ref "D8") (pin "A") (pinfunction "A_A") (pintype "passive"))
      (node (ref "Q2") (pin "2") (pinfunction "D_2") (pintype "passive"))
    )
    (net (code "109") (name "Net-(Q2-S)") (class "Default")
      (node (ref "B1") (pin "-") (pinfunction "-_-") (pintype "passive"))
      (node (ref "C6") (pin "-") (pinfunction "-_-") (pintype "passive"))
      (node (ref "CX2") (pin "2") (pinfunction "2_2") (pintype "passive"))
      (node (ref "D9") (pin "A") (pinfunction "A_A") (pintype "passive"))
      (node (ref "Q2") (pin "3") (pinfunction "S_3") (pintype "passive"))
      (node (ref "R15") (pin "1") (pinfunction "1_1") (pintype "passive"))
    )
    (net (code "110") (name "Net-(Q3-S)") (class "Default")
      (node (ref "Q3") (pin "1") (pinfunction "S_1") (pintype "bidirectional"))
      (node (ref "R22") (pin "2") (pinfunction "2_2") (pintype "passive"))
      (node (ref "SK1") (pin "3") (pinfunction "SDA0_3") (pintype "bidirectional"))
    )
    (net (code "111") (name "Net-(Q5-S)") (class "Default")
      (node (ref "Q5") (pin "1") (pinfunction "S_1") (pintype "bidirectional"))
      (node (ref "R21") (pin "2") (pinfunction "2_2") (pintype "passive"))
      (node (ref "SK1") (pin "5") (pinfunction "SCL0_5") (pintype "bidirectional"))
    )
    (net (code "112") (name "Net-(R16-Pad2)") (class "Default")
      (node (ref "R16") (pin "2") (pinfunction "2_2") (pintype "passive"))
      (node (ref "R17") (pin "1") (pinfunction "1_1") (pintype "passive"))
    )
    (net (code "113") (name "Net-(SK1-+5V0)") (class "Default")
      (node (ref "JP10") (pin "1") (pinfunction "1_1") (pintype "passive"))
      (node (ref "SK1") (pin "2") (pinfunction "+5V0_2") (pintype "power_in"))
    )
    (net (code "114") (name "Net-(SK1-GPIO_GEN1)") (class "Default")
      (node (ref "R18") (pin "2") (pinfunction "2_2") (pintype "passive"))
      (node (ref "SK1") (pin "12") (pinfunction "GPIO_GEN1_12") (pintype "bidirectional"))
    )
    (net (code "115") (name "Net-(SK1-RXD0)") (class "Default")
      (node (ref "SK1") (pin "10") (pinfunction "RXD0_10") (pintype "bidirectional"))
      (node (ref "U$1") (pin "OUT") (pinfunction "OUT_OUT") (pintype "bidirectional"))
    )
    (net (code "116") (name "Net-(T2-B)") (class "Default")
      (node (ref "R13") (pin "2") (pinfunction "2_2") (pintype "passive"))
      (node (ref "T2") (pin "2") (pinfunction "B_2") (pintype "passive"))
    )
    (net (code "117") (name "VCC") (class "Default")
      (node (ref "C3") (pin "1") (pinfunction "1_1") (pintype "passive"))
      (node (ref "C4") (pin "1") (pinfunction "1_1") (pintype "passive"))
      (node (ref "C5") (pin "+") (pinfunction "+_+") (pintype "passive"))
      (node (ref "D2") (pin "A") (pinfunction "A_A") (pintype "passive"))
      (node (ref "D4") (pin "C") (pinfunction "C_C") (pintype "passive"))
      (node (ref "IC1") (pin "18") (pinfunction "~{RESET}_18") (pintype "input"))
      (node (ref "IC1") (pin "9") (pinfunction "VDD_9") (pintype "power_in"))
      (node (ref "IC2") (pin "18") (pinfunction "~{RESET}_18") (pintype "input"))
      (node (ref "IC2") (pin "9") (pinfunction "VDD_9") (pintype "power_in"))
      (node (ref "IC3") (pin "10") (pinfunction "CD+_10") (pintype "passive"))
      (node (ref "IC4") (pin "16") (pinfunction "VCC1_16") (pintype "power_in"))
      (node (ref "IC4") (pin "8") (pinfunction "VCC2_8") (pintype "power_in"))
      (node (ref "J2") (pin "3") (pinfunction "3_3") (pintype "passive"))
      (node (ref "JP10") (pin "2") (pinfunction "2_2") (pintype "passive"))
      (node (ref "K2") (pin "1") (pinfunction "1_1") (pintype "passive"))
      (node (ref "LED1") (pin "A") (pinfunction "A_A") (pintype "passive"))
      (node (ref "OK3") (pin "10") (pinfunction "EMITTER1_10") (pintype "passive"))
      (node (ref "R19") (pin "2") (pinfunction "2_2") (pintype "passive"))
      (node (ref "R2") (pin "2") (pinfunction "2_2") (pintype "passive"))
      (node (ref "R20") (pin "2") (pinfunction "2_2") (pintype "passive"))
      (node (ref "R3") (pin "2") (pinfunction "2_2") (pintype "passive"))
      (node (ref "R4") (pin "2") (pinfunction "2_2") (pintype "passive"))
      (node (ref "R5") (pin "2") (pinfunction "2_2") (pintype "passive"))
      (node (ref "R6") (pin "2") (pinfunction "2_2") (pintype "passive"))
      (node (ref "R7") (pin "2") (pinfunction "2_2") (pintype "passive"))
    )
    (net (code "118") (name "VDD") (class "Default")
      (node (ref "C2") (pin "1") (pinfunction "1_1") (pintype "passive"))
      (node (ref "IC5") (pin "18") (pinfunction "~{RESET}_18") (pintype "input"))
      (node (ref "IC5") (pin "9") (pinfunction "VDD_9") (pintype "power_in"))
      (node (ref "JP7") (pin "3") (pinfunction "3_3") (pintype "passive"))
      (node (ref "JP8") (pin "3") (pinfunction "3_3") (pintype "passive"))
      (node (ref "Q3") (pin "2") (pinfunction "G_2") (pintype "tri_state"))
      (node (ref "Q5") (pin "2") (pinfunction "G_2") (pintype "tri_state"))
      (node (ref "R21") (pin "1") (pinfunction "1_1") (pintype "passive"))
      (node (ref "R22") (pin "1") (pinfunction "1_1") (pintype "passive"))
      (node (ref "SK1") (pin "1") (pinfunction "+3V3_1") (pintype "power_in"))
      (node (ref "U$1") (pin "VCC") (pinfunction "V+_VCC") (pintype "bidirectional"))
    )
    (net (code "119") (name "unconnected-(IC1-INTA-Pad20)") (class "Default")
      (node (ref "IC1") (pin "20") (pinfunction "INTA_20") (pintype "output"))
    )
    (net (code "120") (name "unconnected-(IC1-INTB-Pad19)") (class "Default")
      (node (ref "IC1") (pin "19") (pinfunction "INTB_19") (pintype "output"))
    )
    (net (code "121") (name "unconnected-(IC2-INTA-Pad20)") (class "Default")
      (node (ref "IC2") (pin "20") (pinfunction "INTA_20") (pintype "output"))
    )
    (net (code "122") (name "unconnected-(IC2-INTB-Pad19)") (class "Default")
      (node (ref "IC2") (pin "19") (pinfunction "INTB_19") (pintype "output"))
    )
    (net (code "123") (name "unconnected-(IC5-INTA-Pad20)") (class "Default")
      (node (ref "IC5") (pin "20") (pinfunction "INTA_20") (pintype "output"))
    )
    (net (code "124") (name "unconnected-(IC5-INTB-Pad19)") (class "Default")
      (node (ref "IC5") (pin "19") (pinfunction "INTB_19") (pintype "output"))
    )
    (net (code "125") (name "unconnected-(JP5-Pad9)") (class "Default")
      (node (ref "JP5") (pin "9") (pinfunction "9_9") (pintype "passive"))
    )
    (net (code "126") (name "unconnected-(JP5-Pad10)") (class "Default")
      (node (ref "JP5") (pin "10") (pinfunction "10_10") (pintype "passive"))
    )
    (net (code "127") (name "unconnected-(K2B-S-PadNO)") (class "Default")
      (node (ref "K2") (pin "NO") (pinfunction "S_NO") (pintype "passive"))
    )
    (net (code "128") (name "unconnected-(OK2-BAS-Pad6)") (class "Default")
      (node (ref "OK2") (pin "6") (pinfunction "BAS_6") (pintype "passive"))
    )
    (net (code "129") (name "unconnected-(SK1-+3V3-Pad17)") (class "Default")
      (node (ref "SK1") (pin "17") (pinfunction "+3V3_17") (pintype "no_connect"))
    )
    (net (code "130") (name "unconnected-(SK1-+5V0-Pad4)") (class "Default")
      (node (ref "SK1") (pin "4") (pinfunction "+5V0_4") (pintype "no_connect"))
    )
    (net (code "131") (name "unconnected-(SK1-GND-Pad9)") (class "Default")
      (node (ref "SK1") (pin "9") (pinfunction "GND_9") (pintype "no_connect"))
    )
    (net (code "132") (name "unconnected-(SK1-GND-Pad14)") (class "Default")
      (node (ref "SK1") (pin "14") (pinfunction "GND_14") (pintype "no_connect"))
    )
    (net (code "133") (name "unconnected-(SK1-GND-Pad20)") (class "Default")
      (node (ref "SK1") (pin "20") (pinfunction "GND_20") (pintype "no_connect"))
    )
    (net (code "134") (name "unconnected-(SK1-GND-Pad25)") (class "Default")
      (node (ref "SK1") (pin "25") (pinfunction "GND_25") (pintype "no_connect"))
    )
    (net (code "135") (name "unconnected-(SK1-TXD0-Pad8)") (class "Default")
      (node (ref "SK1") (pin "8") (pinfunction "TXD0_8") (pintype "bidirectional"))
    )
    (net (code "136") (name "unconnected-(SK1-~{SPI_CE1}-Pad26)") (class "Default")
      (node (ref "SK1") (pin "26") (pinfunction "~{SPI_CE1}_26") (pintype "bidirectional"))
    )
  )
)
